# PCB_v1.net
KiCad netlist of a schematic drawn in EAGLE
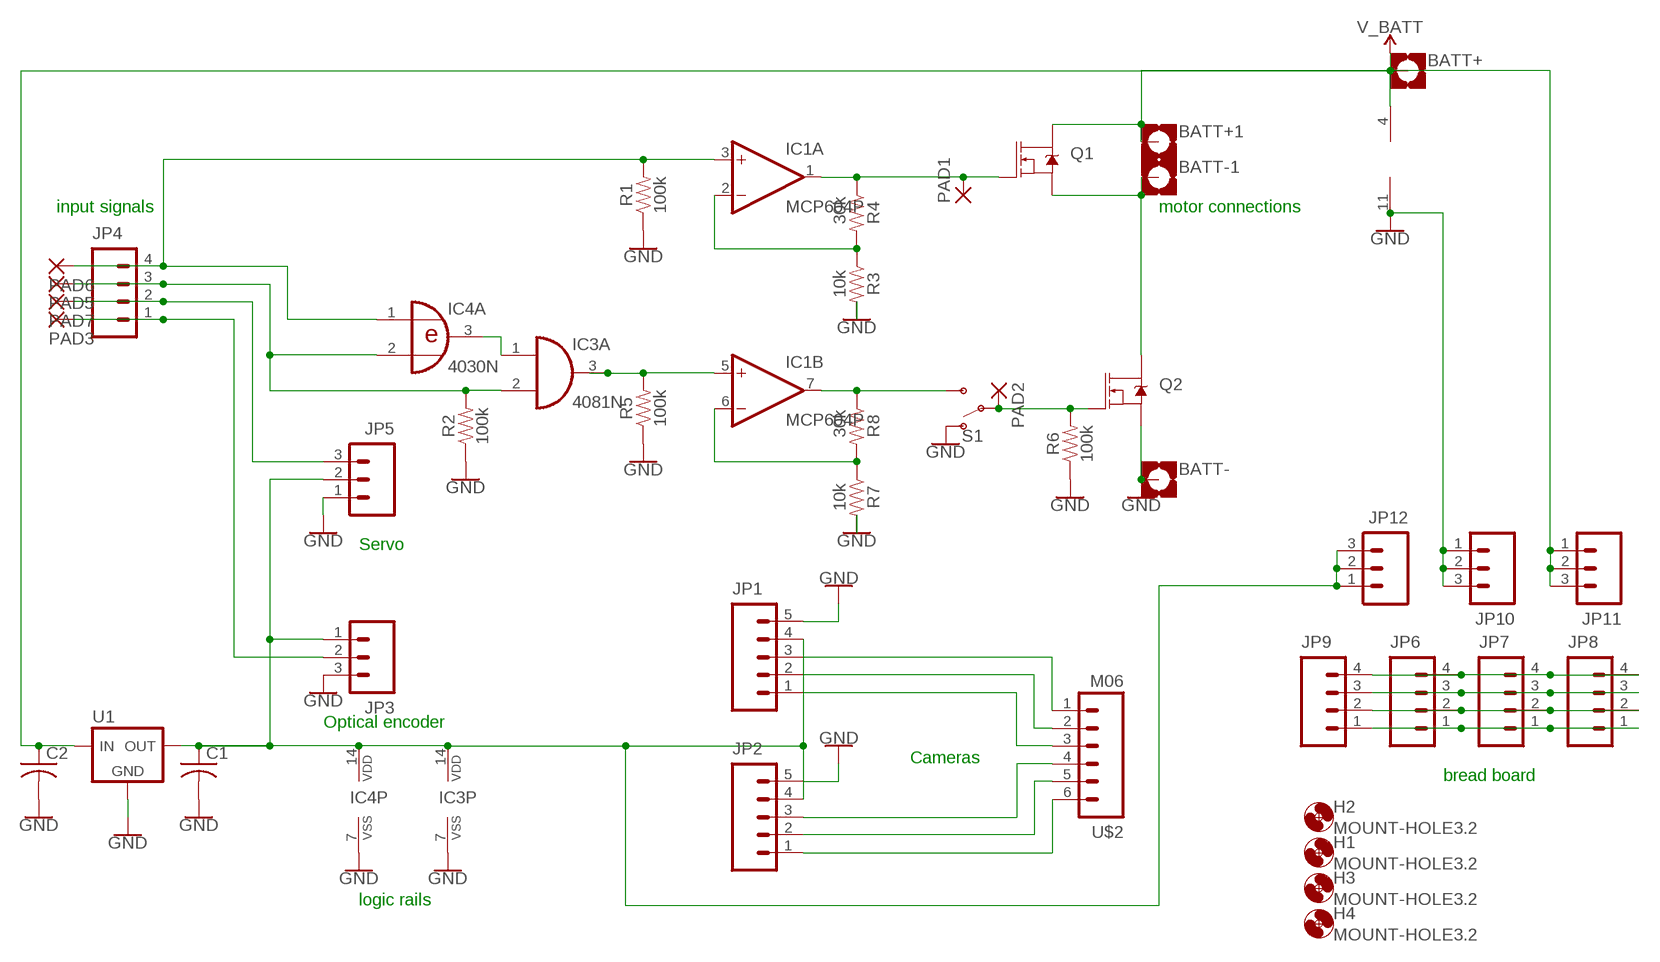
[diagram p0: schematic, sheet 1]

(export (version "E")
  (design (tool "Eeschema 10.0.6"))
  (components
    (comp (ref "BATT+")
      (value "MOUNT-PAD-SQUARE3.0")
      (footprint "eagle-import:3,0-PAD-SQUARE")
      (libsource (lib "eagle-import") (part "MOUNT-PAD-SQUARE3.0"))
    )
    (comp (ref "BATT+1")
      (value "MOUNT-PAD-SQUARE3.0")
      (footprint "eagle-import:3,0-PAD-SQUARE")
      (libsource (lib "eagle-import") (part "MOUNT-PAD-SQUARE3.0"))
    )
    (comp (ref "BATT-")
      (value "MOUNT-PAD-SQUARE3.0")
      (footprint "eagle-import:3,0-PAD-SQUARE")
      (libsource (lib "eagle-import") (part "MOUNT-PAD-SQUARE3.0"))
    )
    (comp (ref "BATT-1")
      (value "MOUNT-PAD-SQUARE3.0")
      (footprint "eagle-import:3,0-PAD-SQUARE")
      (libsource (lib "eagle-import") (part "MOUNT-PAD-SQUARE3.0"))
    )
    (comp (ref "C1")
      (value "C-075PTH")
      (footprint "eagle-import:C075")
      (libsource (lib "eagle-import") (part "C-075PTH"))
    )
    (comp (ref "C2")
      (value "C-075PTH")
      (footprint "eagle-import:C075")
      (libsource (lib "eagle-import") (part "C-075PTH"))
    )
    (comp (ref "H1")
      (value "MOUNT-HOLE3.2")
      (footprint "eagle-import:3,2")
      (libsource (lib "eagle-import") (part "MOUNT-HOLE3.2"))
    )
    (comp (ref "H2")
      (value "MOUNT-HOLE3.2")
      (footprint "eagle-import:3,2")
      (libsource (lib "eagle-import") (part "MOUNT-HOLE3.2"))
    )
    (comp (ref "H3")
      (value "MOUNT-HOLE3.2")
      (footprint "eagle-import:3,2")
      (libsource (lib "eagle-import") (part "MOUNT-HOLE3.2"))
    )
    (comp (ref "H4")
      (value "MOUNT-HOLE3.2")
      (footprint "eagle-import:3,2")
      (libsource (lib "eagle-import") (part "MOUNT-HOLE3.2"))
    )
    (comp (ref "IC1")
      (value "MCP604P")
      (footprint "eagle-import:DIL14")
      (libsource (lib "eagle-import") (part "MCP604P"))
    )
    (comp (ref "IC3")
      (value "4081N")
      (footprint "eagle-import:DIL14")
      (libsource (lib "eagle-import") (part "4081N"))
    )
    (comp (ref "IC4")
      (value "4030N")
      (footprint "eagle-import:DIL14")
      (libsource (lib "eagle-import") (part "4030N"))
    )
    (comp (ref "JP1")
      (value "M05PTH")
      (footprint "eagle-import:1X05")
      (libsource (lib "eagle-import") (part "M05PTH"))
    )
    (comp (ref "JP2")
      (value "M05PTH")
      (footprint "eagle-import:1X05")
      (libsource (lib "eagle-import") (part "M05PTH"))
    )
    (comp (ref "JP3")
      (value "M03PTH")
      (footprint "eagle-import:1X03")
      (libsource (lib "eagle-import") (part "M03PTH"))
    )
    (comp (ref "JP4")
      (value "M04PTH")
      (footprint "eagle-import:1X04")
      (libsource (lib "eagle-import") (part "M04PTH"))
    )
    (comp (ref "JP5")
      (value "M03PTH")
      (footprint "eagle-import:1X03")
      (libsource (lib "eagle-import") (part "M03PTH"))
    )
    (comp (ref "JP6")
      (value "M04PTH")
      (footprint "eagle-import:1X04")
      (libsource (lib "eagle-import") (part "M04PTH"))
    )
    (comp (ref "JP7")
      (value "M04PTH")
      (footprint "eagle-import:1X04")
      (libsource (lib "eagle-import") (part "M04PTH"))
    )
    (comp (ref "JP8")
      (value "M04PTH")
      (footprint "eagle-import:1X04")
      (libsource (lib "eagle-import") (part "M04PTH"))
    )
    (comp (ref "JP9")
      (value "M04PTH")
      (footprint "eagle-import:1X04")
      (libsource (lib "eagle-import") (part "M04PTH"))
    )
    (comp (ref "JP10")
      (value "M03PTH")
      (footprint "eagle-import:1X03")
      (libsource (lib "eagle-import") (part "M03PTH"))
    )
    (comp (ref "JP11")
      (value "M03PTH")
      (footprint "eagle-import:1X03")
      (libsource (lib "eagle-import") (part "M03PTH"))
    )
    (comp (ref "JP12")
      (value "M03PTH")
      (footprint "eagle-import:1X03")
      (libsource (lib "eagle-import") (part "M03PTH"))
    )
    (comp (ref "PAD1")
      (value "2,15/1,0")
      (footprint "eagle-import:2,15_1,0")
      (libsource (lib "eagle-import") (part "2,15/1,0"))
    )
    (comp (ref "PAD2")
      (value "2,15/1,0")
      (footprint "eagle-import:2,15_1,0")
      (libsource (lib "eagle-import") (part "2,15/1,0"))
    )
    (comp (ref "PAD3")
      (value "2,15/1,0")
      (footprint "eagle-import:2,15_1,0")
      (libsource (lib "eagle-import") (part "2,15/1,0"))
    )
    (comp (ref "PAD5")
      (value "2,15/1,0")
      (footprint "eagle-import:2,15_1,0")
      (libsource (lib "eagle-import") (part "2,15/1,0"))
    )
    (comp (ref "PAD6")
      (value "2,15/1,0")
      (footprint "eagle-import:2,15_1,0")
      (libsource (lib "eagle-import") (part "2,15/1,0"))
    )
    (comp (ref "PAD7")
      (value "2,15/1,0")
      (footprint "eagle-import:2,15_1,0")
      (libsource (lib "eagle-import") (part "2,15/1,0"))
    )
    (comp (ref "Q1")
      (value "MOSFET-NCH-FQP30N06L")
      (footprint "eagle-import:TO220V")
      (libsource (lib "eagle-import") (part "MOSFET-NCH-FQP30N06L"))
    )
    (comp (ref "Q2")
      (value "MOSFET-NCH-FQP30N06L")
      (footprint "eagle-import:TO220V")
      (libsource (lib "eagle-import") (part "MOSFET-NCH-FQP30N06L"))
    )
    (comp (ref "R1")
      (value "100k")
      (footprint "eagle-import:AXIAL-0.3")
      (libsource (lib "eagle-import") (part "10KOHM-HORIZ-1/4W-1%"))
    )
    (comp (ref "R2")
      (value "100k")
      (footprint "eagle-import:AXIAL-0.3")
      (libsource (lib "eagle-import") (part "10KOHM-HORIZ-1/4W-1%"))
    )
    (comp (ref "R3")
      (value "10k")
      (footprint "eagle-import:AXIAL-0.3")
      (libsource (lib "eagle-import") (part "10KOHM-HORIZ-1/4W-1%"))
    )
    (comp (ref "R4")
      (value "30k")
      (footprint "eagle-import:AXIAL-0.3")
      (libsource (lib "eagle-import") (part "RESISTORAXIAL-0.3"))
    )
    (comp (ref "R5")
      (value "100k")
      (footprint "eagle-import:AXIAL-0.3")
      (libsource (lib "eagle-import") (part "10KOHM-HORIZ-1/4W-1%"))
    )
    (comp (ref "R6")
      (value "100k")
      (footprint "eagle-import:AXIAL-0.3")
      (libsource (lib "eagle-import") (part "10KOHM-HORIZ-1/4W-1%"))
    )
    (comp (ref "R7")
      (value "10k")
      (footprint "eagle-import:AXIAL-0.3")
      (libsource (lib "eagle-import") (part "10KOHM-HORIZ-1/4W-1%"))
    )
    (comp (ref "R8")
      (value "30k")
      (footprint "eagle-import:AXIAL-0.3")
      (libsource (lib "eagle-import") (part "RESISTORAXIAL-0.3"))
    )
    (comp (ref "S1")
      (value "SWITCH-SPDT-PTH-11.6X4.0MM-KIT")
      (footprint "eagle-import:SWITCH_SPDT_PTH_11.6X4.0MM_KIT")
      (libsource (lib "eagle-import") (part "SWITCH-SPDT-PTH-11.6X4.0MM-KIT"))
    )
    (comp (ref "U$2")
      (value "M06")
      (footprint "eagle-import:1X06-MTA")
      (libsource (lib "eagle-import") (part "M06"))
    )
    (comp (ref "U1")
      (value "78XX-TO220V")
      (footprint "eagle-import:TO220BV")
      (libsource (lib "eagle-import") (part "78XX-TO220V"))
    )
  )
  (nets
    (net (code "1") (name "GND") (class "Default")
      (node (ref "BATT-") (pin "B3,0") (pinfunction "MOUNT_B3,0") (pintype "passive"))
      (node (ref "C1") (pin "2") (pinfunction "-_2") (pintype "passive"))
      (node (ref "C2") (pin "2") (pinfunction "-_2") (pintype "passive"))
      (node (ref "IC1") (pin "11") (pinfunction "V-_11") (pintype "power_in"))
      (node (ref "IC3") (pin "7") (pinfunction "VSS_7") (pintype "power_in"))
      (node (ref "IC4") (pin "7") (pinfunction "VSS_7") (pintype "power_in"))
      (node (ref "JP1") (pin "5") (pinfunction "5_5") (pintype "passive"))
      (node (ref "JP10") (pin "1") (pinfunction "1_1") (pintype "passive"))
      (node (ref "JP10") (pin "2") (pinfunction "2_2") (pintype "passive"))
      (node (ref "JP10") (pin "3") (pinfunction "3_3") (pintype "passive"))
      (node (ref "JP2") (pin "5") (pinfunction "5_5") (pintype "passive"))
      (node (ref "JP3") (pin "3") (pinfunction "3_3") (pintype "passive"))
      (node (ref "JP5") (pin "1") (pinfunction "1_1") (pintype "passive"))
      (node (ref "Q2") (pin "3") (pinfunction "S_3") (pintype "bidirectional"))
      (node (ref "R1") (pin "P$1") (pinfunction "1_P$1") (pintype "passive"))
      (node (ref "R2") (pin "P$1") (pinfunction "1_P$1") (pintype "passive"))
      (node (ref "R3") (pin "P$2") (pinfunction "2_P$2") (pintype "passive"))
      (node (ref "R5") (pin "P$1") (pinfunction "1_P$1") (pintype "passive"))
      (node (ref "R6") (pin "P$1") (pinfunction "1_P$1") (pintype "passive"))
      (node (ref "R7") (pin "P$2") (pinfunction "2_P$2") (pintype "passive"))
      (node (ref "S1") (pin "1") (pinfunction "O_1") (pintype "passive"))
      (node (ref "U1") (pin "2") (pinfunction "GND_2") (pintype "power_in"))
    )
    (net (code "2") (name "Net-(BATT-1-MOUNT)") (class "Default")
      (node (ref "BATT-1") (pin "B3,0") (pinfunction "MOUNT_B3,0") (pintype "passive"))
      (node (ref "Q1") (pin "3") (pinfunction "S_3") (pintype "bidirectional"))
      (node (ref "Q2") (pin "2") (pinfunction "D_2") (pintype "bidirectional"))
    )
    (net (code "3") (name "Net-(C1-+)") (class "Default")
      (node (ref "C1") (pin "1") (pinfunction "+_1") (pintype "passive"))
      (node (ref "IC3") (pin "14") (pinfunction "VDD_14") (pintype "power_in"))
      (node (ref "IC4") (pin "14") (pinfunction "VDD_14") (pintype "power_in"))
      (node (ref "JP1") (pin "4") (pinfunction "4_4") (pintype "passive"))
      (node (ref "JP12") (pin "1") (pinfunction "1_1") (pintype "passive"))
      (node (ref "JP12") (pin "2") (pinfunction "2_2") (pintype "passive"))
      (node (ref "JP12") (pin "3") (pinfunction "3_3") (pintype "passive"))
      (node (ref "JP2") (pin "4") (pinfunction "4_4") (pintype "passive"))
      (node (ref "JP3") (pin "1") (pinfunction "1_1") (pintype "passive"))
      (node (ref "JP5") (pin "2") (pinfunction "2_2") (pintype "passive"))
      (node (ref "U1") (pin "3") (pinfunction "VOUT_3") (pintype "power_in"))
    )
    (net (code "4") (name "Net-(IC1A-+IN)") (class "Default")
      (node (ref "IC1") (pin "3") (pinfunction "+IN_3") (pintype "input"))
      (node (ref "IC4") (pin "1") (pinfunction "I0_1") (pintype "input"))
      (node (ref "JP4") (pin "4") (pinfunction "4_4") (pintype "passive"))
      (node (ref "PAD6") (pin "1") (pinfunction "P_1") (pintype "passive"))
      (node (ref "R1") (pin "P$2") (pinfunction "2_P$2") (pintype "passive"))
    )
    (net (code "5") (name "Net-(IC1A--IN)") (class "Default")
      (node (ref "IC1") (pin "2") (pinfunction "-IN_2") (pintype "input"))
      (node (ref "R3") (pin "P$1") (pinfunction "1_P$1") (pintype "passive"))
      (node (ref "R4") (pin "P$2") (pinfunction "2_P$2") (pintype "passive"))
    )
    (net (code "6") (name "Net-(IC1A-OUT)") (class "Default")
      (node (ref "IC1") (pin "1") (pinfunction "OUT_1") (pintype "output"))
      (node (ref "PAD1") (pin "1") (pinfunction "P_1") (pintype "passive"))
      (node (ref "Q1") (pin "1") (pinfunction "G_1") (pintype "bidirectional"))
      (node (ref "R4") (pin "P$1") (pinfunction "1_P$1") (pintype "passive"))
    )
    (net (code "7") (name "Net-(IC1B-+IN)") (class "Default")
      (node (ref "IC1") (pin "5") (pinfunction "+IN_5") (pintype "input"))
      (node (ref "IC3") (pin "3") (pinfunction "O_3") (pintype "output"))
      (node (ref "R5") (pin "P$2") (pinfunction "2_P$2") (pintype "passive"))
    )
    (net (code "8") (name "Net-(IC1B--IN)") (class "Default")
      (node (ref "IC1") (pin "6") (pinfunction "-IN_6") (pintype "input"))
      (node (ref "R7") (pin "P$1") (pinfunction "1_P$1") (pintype "passive"))
      (node (ref "R8") (pin "P$2") (pinfunction "2_P$2") (pintype "passive"))
    )
    (net (code "9") (name "Net-(IC1B-OUT)") (class "Default")
      (node (ref "IC1") (pin "7") (pinfunction "OUT_7") (pintype "output"))
      (node (ref "R8") (pin "P$1") (pinfunction "1_P$1") (pintype "passive"))
      (node (ref "S1") (pin "3") (pinfunction "S_3") (pintype "passive"))
    )
    (net (code "10") (name "Net-(IC3A-I0)") (class "Default")
      (node (ref "IC3") (pin "1") (pinfunction "I0_1") (pintype "input"))
      (node (ref "IC4") (pin "3") (pinfunction "O_3") (pintype "output"))
    )
    (net (code "11") (name "Net-(IC3A-I1)") (class "Default")
      (node (ref "IC3") (pin "2") (pinfunction "I1_2") (pintype "input"))
      (node (ref "IC4") (pin "2") (pinfunction "I1_2") (pintype "input"))
      (node (ref "JP4") (pin "3") (pinfunction "3_3") (pintype "passive"))
      (node (ref "PAD5") (pin "1") (pinfunction "P_1") (pintype "passive"))
      (node (ref "R2") (pin "P$2") (pinfunction "2_P$2") (pintype "passive"))
    )
    (net (code "12") (name "Net-(JP1-Pad1)") (class "Default")
      (node (ref "JP1") (pin "1") (pinfunction "1_1") (pintype "passive"))
      (node (ref "U$2") (pin "3") (pinfunction "3_3") (pintype "passive"))
    )
    (net (code "13") (name "Net-(JP1-Pad2)") (class "Default")
      (node (ref "JP1") (pin "2") (pinfunction "2_2") (pintype "passive"))
      (node (ref "U$2") (pin "2") (pinfunction "2_2") (pintype "passive"))
    )
    (net (code "14") (name "Net-(JP1-Pad3)") (class "Default")
      (node (ref "JP1") (pin "3") (pinfunction "3_3") (pintype "passive"))
      (node (ref "U$2") (pin "1") (pinfunction "1_1") (pintype "passive"))
    )
    (net (code "15") (name "Net-(JP2-Pad1)") (class "Default")
      (node (ref "JP2") (pin "1") (pinfunction "1_1") (pintype "passive"))
      (node (ref "U$2") (pin "6") (pinfunction "6_6") (pintype "passive"))
    )
    (net (code "16") (name "Net-(JP2-Pad2)") (class "Default")
      (node (ref "JP2") (pin "2") (pinfunction "2_2") (pintype "passive"))
      (node (ref "U$2") (pin "5") (pinfunction "5_5") (pintype "passive"))
    )
    (net (code "17") (name "Net-(JP2-Pad3)") (class "Default")
      (node (ref "JP2") (pin "3") (pinfunction "3_3") (pintype "passive"))
      (node (ref "U$2") (pin "4") (pinfunction "4_4") (pintype "passive"))
    )
    (net (code "18") (name "Net-(JP6-Pad1)") (class "Default")
      (node (ref "JP6") (pin "1") (pinfunction "1_1") (pintype "passive"))
      (node (ref "JP7") (pin "1") (pinfunction "1_1") (pintype "passive"))
      (node (ref "JP8") (pin "1") (pinfunction "1_1") (pintype "passive"))
      (node (ref "JP9") (pin "1") (pinfunction "1_1") (pintype "passive"))
    )
    (net (code "19") (name "Net-(JP6-Pad2)") (class "Default")
      (node (ref "JP6") (pin "2") (pinfunction "2_2") (pintype "passive"))
      (node (ref "JP7") (pin "2") (pinfunction "2_2") (pintype "passive"))
      (node (ref "JP8") (pin "2") (pinfunction "2_2") (pintype "passive"))
      (node (ref "JP9") (pin "2") (pinfunction "2_2") (pintype "passive"))
    )
    (net (code "20") (name "Net-(JP6-Pad3)") (class "Default")
      (node (ref "JP6") (pin "3") (pinfunction "3_3") (pintype "passive"))
      (node (ref "JP7") (pin "3") (pinfunction "3_3") (pintype "passive"))
      (node (ref "JP8") (pin "3") (pinfunction "3_3") (pintype "passive"))
      (node (ref "JP9") (pin "3") (pinfunction "3_3") (pintype "passive"))
    )
    (net (code "21") (name "Net-(JP6-Pad4)") (class "Default")
      (node (ref "JP6") (pin "4") (pinfunction "4_4") (pintype "passive"))
      (node (ref "JP7") (pin "4") (pinfunction "4_4") (pintype "passive"))
      (node (ref "JP8") (pin "4") (pinfunction "4_4") (pintype "passive"))
      (node (ref "JP9") (pin "4") (pinfunction "4_4") (pintype "passive"))
    )
    (net (code "22") (name "Net-(PAD2-P)") (class "Default")
      (node (ref "PAD2") (pin "1") (pinfunction "P_1") (pintype "passive"))
      (node (ref "Q2") (pin "1") (pinfunction "G_1") (pintype "bidirectional"))
      (node (ref "R6") (pin "P$2") (pinfunction "2_P$2") (pintype "passive"))
      (node (ref "S1") (pin "2") (pinfunction "P_2") (pintype "passive"))
    )
    (net (code "23") (name "Net-(PAD3-P)") (class "Default")
      (node (ref "JP3") (pin "2") (pinfunction "2_2") (pintype "passive"))
      (node (ref "JP4") (pin "1") (pinfunction "1_1") (pintype "passive"))
      (node (ref "PAD3") (pin "1") (pinfunction "P_1") (pintype "passive"))
    )
    (net (code "24") (name "Net-(PAD7-P)") (class "Default")
      (node (ref "JP4") (pin "2") (pinfunction "2_2") (pintype "passive"))
      (node (ref "JP5") (pin "3") (pinfunction "3_3") (pintype "passive"))
      (node (ref "PAD7") (pin "1") (pinfunction "P_1") (pintype "passive"))
    )
    (net (code "25") (name "V_BATT") (class "Default")
      (node (ref "BATT+") (pin "B3,0") (pinfunction "MOUNT_B3,0") (pintype "passive"))
      (node (ref "BATT+1") (pin "B3,0") (pinfunction "MOUNT_B3,0") (pintype "passive"))
      (node (ref "C2") (pin "1") (pinfunction "+_1") (pintype "passive"))
      (node (ref "IC1") (pin "4") (pinfunction "V+_4") (pintype "power_in"))
      (node (ref "JP11") (pin "1") (pinfunction "1_1") (pintype "passive"))
      (node (ref "JP11") (pin "2") (pinfunction "2_2") (pintype "passive"))
      (node (ref "JP11") (pin "3") (pinfunction "3_3") (pintype "passive"))
      (node (ref "Q1") (pin "2") (pinfunction "D_2") (pintype "bidirectional"))
      (node (ref "U1") (pin "1") (pinfunction "VIN_1") (pintype "power_in"))
    )
  )
)
